# POWER.net
KiCad netlist of a schematic drawn in Altium Designer
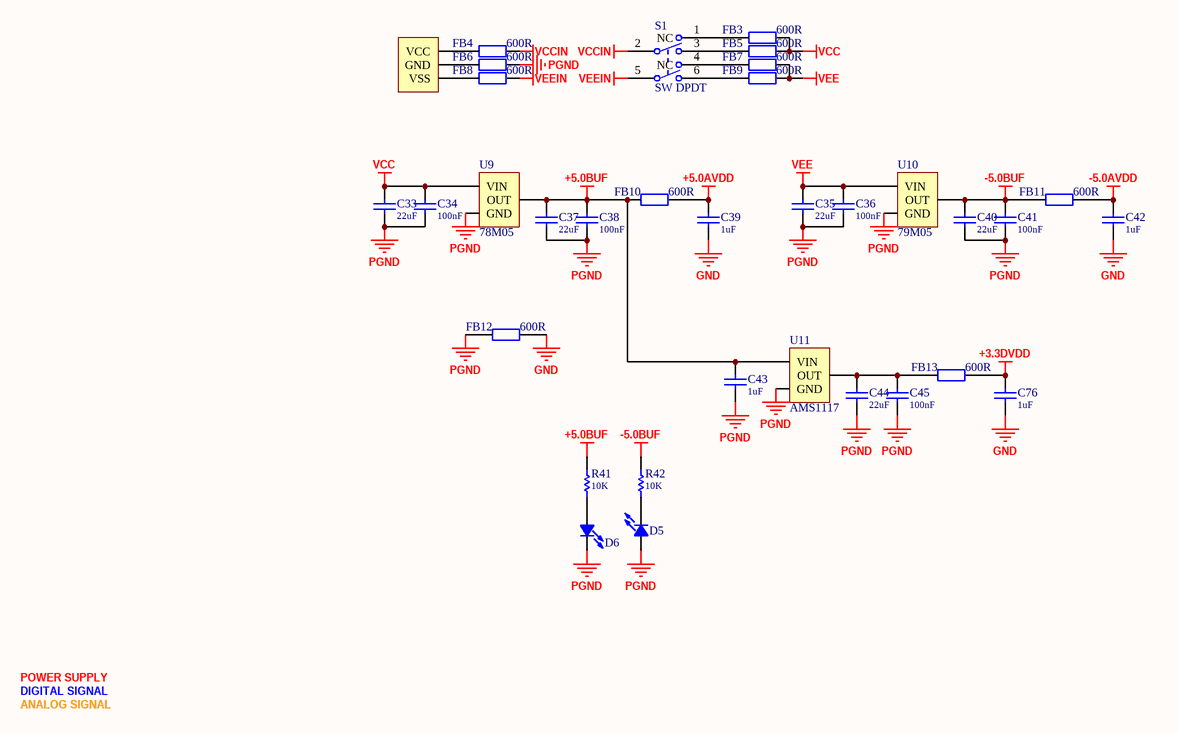
[diagram p0: POWER.SchDoc]

(export (version "E")
  (design (tool "Eeschema 10.0.6"))
  (components
    (comp (ref "C33")
      (value "22uF")
      (footprint "C0805-L")
      (description "贴片瓷片电容")
      (fields (field (name "Comment") "Cap-S"))
      (libsource (lib "xz_D") (part "Cap-S"))
    )
    (comp (ref "C34")
      (value "100nF")
      (footprint "C0603-L")
      (description "贴片瓷片电容")
      (fields (field (name "Comment") "Cap-S"))
      (libsource (lib "xz_D") (part "Cap-S"))
    )
    (comp (ref "C35")
      (value "22uF")
      (footprint "C0805-L")
      (description "贴片瓷片电容")
      (fields (field (name "Comment") "Cap-S"))
      (libsource (lib "xz_D") (part "Cap-S"))
    )
    (comp (ref "C36")
      (value "100nF")
      (footprint "C0603-L")
      (description "贴片瓷片电容")
      (fields (field (name "Comment") "Cap-S"))
      (libsource (lib "xz_D") (part "Cap-S"))
    )
    (comp (ref "C37")
      (value "22uF")
      (footprint "C0805-L")
      (description "贴片瓷片电容")
      (fields (field (name "Comment") "Cap-S"))
      (libsource (lib "xz_D") (part "Cap-S"))
    )
    (comp (ref "C38")
      (value "100nF")
      (footprint "C0603-L")
      (description "贴片瓷片电容")
      (fields (field (name "Comment") "Cap-S"))
      (libsource (lib "xz_D") (part "Cap-S"))
    )
    (comp (ref "C39")
      (value "1uF")
      (footprint "C0603-L")
      (description "贴片瓷片电容")
      (fields (field (name "Comment") "Cap-S"))
      (libsource (lib "xz_D") (part "Cap-S"))
    )
    (comp (ref "C40")
      (value "22uF")
      (footprint "C0805-L")
      (description "贴片瓷片电容")
      (fields (field (name "Comment") "Cap-S"))
      (libsource (lib "xz_D") (part "Cap-S"))
    )
    (comp (ref "C41")
      (value "100nF")
      (footprint "C0603-L")
      (description "贴片瓷片电容")
      (fields (field (name "Comment") "Cap-S"))
      (libsource (lib "xz_D") (part "Cap-S"))
    )
    (comp (ref "C42")
      (value "1uF")
      (footprint "C0603-L")
      (description "贴片瓷片电容")
      (fields (field (name "Comment") "Cap-S"))
      (libsource (lib "xz_D") (part "Cap-S"))
    )
    (comp (ref "C43")
      (value "1uF")
      (footprint "C0603-L")
      (description "贴片瓷片电容")
      (fields (field (name "Comment") "Cap-S"))
      (libsource (lib "xz_D") (part "Cap-S"))
    )
    (comp (ref "C44")
      (value "22uF")
      (footprint "C0805-L")
      (description "贴片瓷片电容")
      (fields (field (name "Comment") "Cap-S"))
      (libsource (lib "xz_D") (part "Cap-S"))
    )
    (comp (ref "C45")
      (value "100nF")
      (footprint "C0603-L")
      (description "贴片瓷片电容")
      (fields (field (name "Comment") "Cap-S"))
      (libsource (lib "xz_D") (part "Cap-S"))
    )
    (comp (ref "C76")
      (value "1uF")
      (footprint "C0603-L")
      (description "贴片瓷片电容")
      (fields (field (name "Comment") "Cap-S"))
      (libsource (lib "xz_D") (part "Cap-S"))
    )
    (comp (ref "D5")
      (value "LED")
      (footprint "Led-0805_L")
      (description "发光二极管")
      (libsource (lib "CommonUsed") (part "LED"))
    )
    (comp (ref "D6")
      (value "LED")
      (footprint "Led-0805_L")
      (description "发光二极管")
      (libsource (lib "CommonUsed") (part "LED"))
    )
    (comp (ref "FB3") (value "600R") (footprint "FB-0805") (libsource (lib "CommonUsed") (part "FB")))
    (comp (ref "FB4") (value "600R") (footprint "FB-0805") (libsource (lib "CommonUsed") (part "FB")))
    (comp (ref "FB5") (value "600R") (footprint "FB-0805") (libsource (lib "CommonUsed") (part "FB")))
    (comp (ref "FB6") (value "600R") (footprint "FB-0805") (libsource (lib "CommonUsed") (part "FB")))
    (comp (ref "FB7") (value "600R") (footprint "FB-0805") (libsource (lib "CommonUsed") (part "FB")))
    (comp (ref "FB8") (value "600R") (footprint "FB-0805") (libsource (lib "CommonUsed") (part "FB")))
    (comp (ref "FB9") (value "600R") (footprint "FB-0805") (libsource (lib "CommonUsed") (part "FB")))
    (comp (ref "FB10") (value "600R") (footprint "FB-0805") (libsource (lib "CommonUsed") (part "FB")))
    (comp (ref "FB11") (value "600R") (footprint "FB-0805") (libsource (lib "CommonUsed") (part "FB")))
    (comp (ref "FB12") (value "600R") (footprint "FB-0805") (libsource (lib "CommonUsed") (part "FB")))
    (comp (ref "FB13") (value "600R") (footprint "FB-0805") (libsource (lib "CommonUsed") (part "FB")))
    (comp (ref "J2")
      (value "Power-3P")
      (footprint "SIPA03")
      (description "供电端子")
      (libsource (lib "xz_C") (part "Power-3P"))
    )
    (comp (ref "R41")
      (value "10K")
      (footprint "R0603-L")
      (description "贴片电阻")
      (fields (field (name "Comment") "R"))
      (libsource (lib "xz_D") (part "Res"))
    )
    (comp (ref "R42")
      (value "10K")
      (footprint "R0603-L")
      (description "贴片电阻")
      (fields (field (name "Comment") "R"))
      (libsource (lib "xz_D") (part "Res"))
    )
    (comp (ref "S1")
      (value "SW DPDT")
      (footprint "SW_DPDT")
      (description "自锁开关")
      (fields (field (name "PUBLISHER") "Altium Limited"))
      (libsource (lib "xz_D") (part "SW DPDT"))
    )
    (comp (ref "U9") (value "78M05") (footprint "TO-252") (libsource (lib "PowerUnits") (part "78M05")))
    (comp (ref "U10") (value "79M05") (footprint "TO-252") (libsource (lib "PowerUnits") (part "79M05")))
    (comp (ref "U11") (value "AMS1117") (footprint "SOT-223") (libsource (lib "CommonUsed") (part "AMS1117")))
  )
  (nets
    (net (code "1") (name "+3.3DVDD") (class "Default")
      (node (ref "C76") (pin "2") (pinfunction "2_2") (pintype "passive"))
      (node (ref "FB13") (pin "2") (pinfunction "2_2") (pintype "passive"))
    )
    (net (code "2") (name "+5.0AVDD") (class "Default")
      (node (ref "C39") (pin "2") (pinfunction "2_2") (pintype "passive"))
      (node (ref "FB10") (pin "2") (pinfunction "2_2") (pintype "passive"))
    )
    (net (code "3") (name "+5.0BUF") (class "Default")
      (node (ref "C37") (pin "2") (pinfunction "2_2") (pintype "passive"))
      (node (ref "C38") (pin "2") (pinfunction "2_2") (pintype "passive"))
      (node (ref "C43") (pin "2") (pinfunction "2_2") (pintype "passive"))
      (node (ref "FB10") (pin "1") (pinfunction "1_1") (pintype "passive"))
      (node (ref "R41") (pin "2") (pinfunction "2_2") (pintype "passive"))
      (node (ref "U11") (pin "3") (pinfunction "VIN_3") (pintype "passive"))
      (node (ref "U9") (pin "3") (pinfunction "OUT_3") (pintype "passive"))
    )
    (net (code "4") (name "-5.0AVDD") (class "Default")
      (node (ref "C42") (pin "2") (pinfunction "2_2") (pintype "passive"))
      (node (ref "FB11") (pin "2") (pinfunction "2_2") (pintype "passive"))
    )
    (net (code "5") (name "-5.0BUF") (class "Default")
      (node (ref "C40") (pin "2") (pinfunction "2_2") (pintype "passive"))
      (node (ref "C41") (pin "2") (pinfunction "2_2") (pintype "passive"))
      (node (ref "FB11") (pin "1") (pinfunction "1_1") (pintype "passive"))
      (node (ref "R42") (pin "2") (pinfunction "2_2") (pintype "passive"))
      (node (ref "U10") (pin "3") (pinfunction "OUT_3") (pintype "passive"))
    )
    (net (code "9") (name "GND") (class "Default")
      (node (ref "C39") (pin "1") (pinfunction "1_1") (pintype "passive"))
      (node (ref "C42") (pin "1") (pinfunction "1_1") (pintype "passive"))
      (node (ref "C76") (pin "1") (pinfunction "1_1") (pintype "passive"))
      (node (ref "FB12") (pin "2") (pinfunction "2_2") (pintype "passive"))
    )
    (net (code "10") (name "Net-(D5-Pad2)") (class "Default")
      (node (ref "D5") (pin "2") (pinfunction "2_2") (pintype "passive"))
      (node (ref "R42") (pin "1") (pinfunction "1_1") (pintype "passive"))
    )
    (net (code "11") (name "Net-(D6-Pad1)") (class "Default")
      (node (ref "D6") (pin "1") (pinfunction "1_1") (pintype "passive"))
      (node (ref "R41") (pin "1") (pinfunction "1_1") (pintype "passive"))
    )
    (net (code "12") (name "Net-(FB3-Pad1)") (class "Default")
      (node (ref "FB3") (pin "1") (pinfunction "1_1") (pintype "passive"))
      (node (ref "S1") (pin "1") (pinfunction "NC_1") (pintype "passive"))
    )
    (net (code "13") (name "Net-(FB7-Pad1)") (class "Default")
      (node (ref "FB7") (pin "1") (pinfunction "1_1") (pintype "passive"))
      (node (ref "S1") (pin "4") (pinfunction "NC_4") (pintype "passive"))
    )
    (net (code "14") (name "Net-(J2-GND)") (class "Default")
      (node (ref "FB6") (pin "1") (pinfunction "1_1") (pintype "passive"))
      (node (ref "J2") (pin "2") (pinfunction "GND_2") (pintype "passive"))
    )
    (net (code "15") (name "Net-(J2-VCC)") (class "Default")
      (node (ref "FB4") (pin "1") (pinfunction "1_1") (pintype "passive"))
      (node (ref "J2") (pin "1") (pinfunction "VCC_1") (pintype "passive"))
    )
    (net (code "16") (name "Net-(J2-VSS)") (class "Default")
      (node (ref "FB8") (pin "1") (pinfunction "1_1") (pintype "passive"))
      (node (ref "J2") (pin "3") (pinfunction "VSS_3") (pintype "passive"))
    )
    (net (code "17") (name "Net-(S1-NO1)") (class "Default")
      (node (ref "FB5") (pin "1") (pinfunction "1_1") (pintype "passive"))
      (node (ref "S1") (pin "3") (pinfunction "NO1_3") (pintype "passive"))
    )
    (net (code "18") (name "Net-(S1-NO2)") (class "Default")
      (node (ref "FB9") (pin "1") (pinfunction "1_1") (pintype "passive"))
      (node (ref "S1") (pin "6") (pinfunction "NO2_6") (pintype "passive"))
    )
    (net (code "19") (name "Net-(U11-OUT)") (class "Default")
      (node (ref "C44") (pin "2") (pinfunction "2_2") (pintype "passive"))
      (node (ref "C45") (pin "2") (pinfunction "2_2") (pintype "passive"))
      (node (ref "FB13") (pin "1") (pinfunction "1_1") (pintype "passive"))
      (node (ref "U11") (pin "2") (pinfunction "OUT_2") (pintype "passive"))
    )
    (net (code "20") (name "PGND") (class "Default")
      (node (ref "C33") (pin "1") (pinfunction "1_1") (pintype "passive"))
      (node (ref "C34") (pin "1") (pinfunction "1_1") (pintype "passive"))
      (node (ref "C35") (pin "1") (pinfunction "1_1") (pintype "passive"))
      (node (ref "C36") (pin "1") (pinfunction "1_1") (pintype "passive"))
      (node (ref "C37") (pin "1") (pinfunction "1_1") (pintype "passive"))
      (node (ref "C38") (pin "1") (pinfunction "1_1") (pintype "passive"))
      (node (ref "C40") (pin "1") (pinfunction "1_1") (pintype "passive"))
      (node (ref "C41") (pin "1") (pinfunction "1_1") (pintype "passive"))
      (node (ref "C43") (pin "1") (pinfunction "1_1") (pintype "passive"))
      (node (ref "C44") (pin "1") (pinfunction "1_1") (pintype "passive"))
      (node (ref "C45") (pin "1") (pinfunction "1_1") (pintype "passive"))
      (node (ref "D5") (pin "1") (pinfunction "1_1") (pintype "passive"))
      (node (ref "D6") (pin "2") (pinfunction "2_2") (pintype "passive"))
      (node (ref "FB12") (pin "1") (pinfunction "1_1") (pintype "passive"))
      (node (ref "FB6") (pin "2") (pinfunction "2_2") (pintype "passive"))
      (node (ref "U10") (pin "1") (pinfunction "GND_1") (pintype "passive"))
      (node (ref "U11") (pin "1") (pinfunction "GND_1") (pintype "passive"))
      (node (ref "U9") (pin "2") (pinfunction "GND_2") (pintype "passive"))
    )
    (net (code "21") (name "VCC") (class "Default")
      (node (ref "C33") (pin "2") (pinfunction "2_2") (pintype "passive"))
      (node (ref "C34") (pin "2") (pinfunction "2_2") (pintype "passive"))
      (node (ref "FB3") (pin "2") (pinfunction "2_2") (pintype "passive"))
      (node (ref "FB5") (pin "2") (pinfunction "2_2") (pintype "passive"))
      (node (ref "U9") (pin "1") (pinfunction "VIN_1") (pintype "passive"))
    )
    (net (code "22") (name "VCCIN") (class "Default")
      (node (ref "FB4") (pin "2") (pinfunction "2_2") (pintype "passive"))
      (node (ref "S1") (pin "2") (pinfunction "1_2") (pintype "passive"))
    )
    (net (code "23") (name "VEE") (class "Default")
      (node (ref "C35") (pin "2") (pinfunction "2_2") (pintype "passive"))
      (node (ref "C36") (pin "2") (pinfunction "2_2") (pintype "passive"))
      (node (ref "FB7") (pin "2") (pinfunction "2_2") (pintype "passive"))
      (node (ref "FB9") (pin "2") (pinfunction "2_2") (pintype "passive"))
      (node (ref "U10") (pin "2") (pinfunction "VIN_2") (pintype "passive"))
    )
    (net (code "24") (name "VEEIN") (class "Default")
      (node (ref "FB8") (pin "2") (pinfunction "2_2") (pintype "passive"))
      (node (ref "S1") (pin "5") (pinfunction "COMMON2_5") (pintype "passive"))
    )
  )
)
